# PARADAS.net
KiCad netlist of a schematic drawn in EAGLE
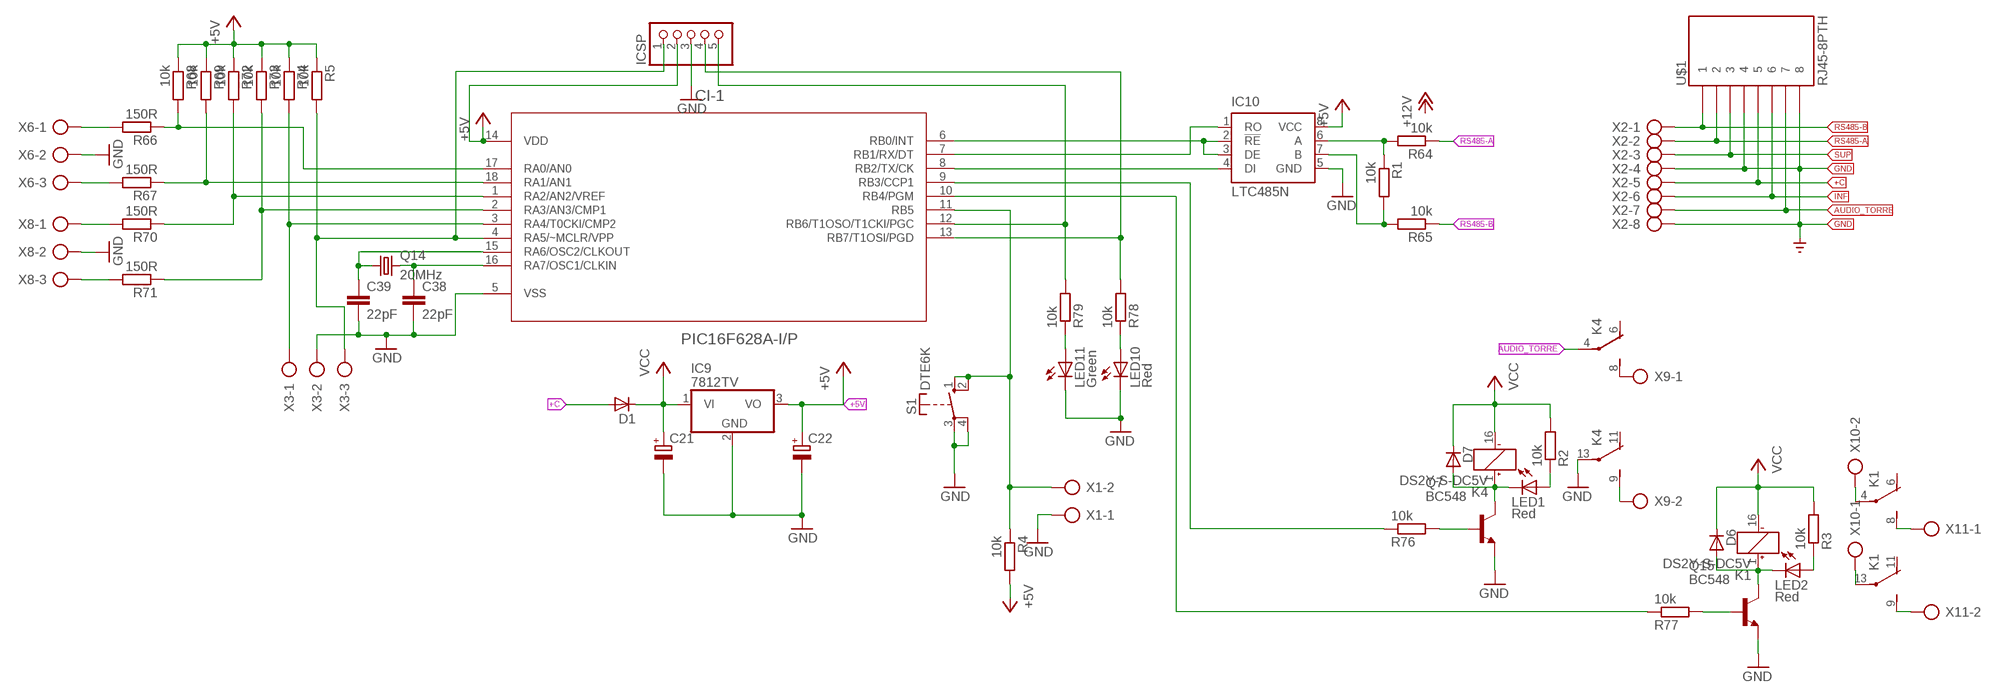
[diagram p0: schematic, sheet 1]

(export (version "E")
  (design (tool "Eeschema 10.0.6"))
  (components
    (comp (ref "C21")
      (value "CPOL-EUE5-13")
      (footprint "eagle-import:E5-13")
      (libsource (lib "eagle-import") (part "CPOL-EUE5-13"))
    )
    (comp (ref "C22")
      (value "CPOL-EUE5-13")
      (footprint "eagle-import:E5-13")
      (libsource (lib "eagle-import") (part "CPOL-EUE5-13"))
    )
    (comp (ref "C38")
      (value "22pF")
      (footprint "eagle-import:C0805")
      (libsource (lib "eagle-import") (part "C-EUC0805"))
    )
    (comp (ref "C39")
      (value "22pF")
      (footprint "eagle-import:C0805")
      (libsource (lib "eagle-import") (part "C-EUC0805"))
    )
    (comp (ref "CI-1")
      (value "PIC16F628A-I/P")
      (footprint "eagle-import:DIP254P762X533-18")
      (libsource (lib "eagle-import") (part "PIC16F628A-I/P"))
    )
    (comp (ref "D1")
      (value "BYS10")
      (footprint "eagle-import:SOD106A")
      (fields (field (name "MPN") "BYS10/45"))
      (libsource (lib "eagle-import") (part "BYS10"))
    )
    (comp (ref "D6")
      (value "BYS10")
      (footprint "eagle-import:SOD106A")
      (fields (field (name "MPN") "BYS10/45"))
      (libsource (lib "eagle-import") (part "BYS10"))
    )
    (comp (ref "D7")
      (value "BYS10")
      (footprint "eagle-import:SOD106A")
      (fields (field (name "MPN") "BYS10/45"))
      (libsource (lib "eagle-import") (part "BYS10"))
    )
    (comp (ref "IC9")
      (value "7812TV")
      (footprint "eagle-import:TO220V")
      (libsource (lib "eagle-import") (part "78TV12"))
    )
    (comp (ref "IC10")
      (value "LTC485N")
      (footprint "eagle-import:DIL08")
      (libsource (lib "eagle-import") (part "LTC485N"))
    )
    (comp (ref "ICSP")
      (value "PINHD-1X5")
      (footprint "eagle-import:1X05")
      (libsource (lib "eagle-import") (part "PINHD-1X5"))
    )
    (comp (ref "K1")
      (value "DS2Y-S-DC5V")
      (footprint "eagle-import:DS2Y")
      (libsource (lib "eagle-import") (part "DS2Y-S-DC5V"))
    )
    (comp (ref "K4")
      (value "DS2Y-S-DC5V")
      (footprint "eagle-import:DS2Y")
      (libsource (lib "eagle-import") (part "DS2Y-S-DC5V"))
    )
    (comp (ref "LED1")
      (value "Red")
      (footprint "eagle-import:LED5MM")
      (libsource (lib "eagle-import") (part "LED5MM"))
    )
    (comp (ref "LED2")
      (value "Red")
      (footprint "eagle-import:LED5MM")
      (libsource (lib "eagle-import") (part "LED5MM"))
    )
    (comp (ref "LED10")
      (value "Red")
      (footprint "eagle-import:LED5MM")
      (libsource (lib "eagle-import") (part "LED5MM"))
    )
    (comp (ref "LED11")
      (value "Green")
      (footprint "eagle-import:LED5MM")
      (libsource (lib "eagle-import") (part "LED5MM"))
    )
    (comp (ref "Q7")
      (value "BC548")
      (footprint "eagle-import:TO92-EBC")
      (libsource (lib "eagle-import") (part "BC548"))
    )
    (comp (ref "Q14")
      (value "20MHz")
      (footprint "eagle-import:HC18U-V")
      (libsource (lib "eagle-import") (part "CRYTALHC18U-V"))
    )
    (comp (ref "Q15")
      (value "BC548")
      (footprint "eagle-import:TO92-EBC")
      (libsource (lib "eagle-import") (part "BC548"))
    )
    (comp (ref "R1")
      (value "10k")
      (footprint "eagle-import:0207_10")
      (libsource (lib "eagle-import") (part "R-EU_0207/10"))
    )
    (comp (ref "R2")
      (value "10k")
      (footprint "eagle-import:0207_10")
      (libsource (lib "eagle-import") (part "R-EU_0207/10"))
    )
    (comp (ref "R3")
      (value "10k")
      (footprint "eagle-import:0207_10")
      (libsource (lib "eagle-import") (part "R-EU_0207/10"))
    )
    (comp (ref "R4")
      (value "10k")
      (footprint "eagle-import:0207_10")
      (libsource (lib "eagle-import") (part "R-EU_0207/10"))
    )
    (comp (ref "R5")
      (value "10k")
      (footprint "eagle-import:0207_10")
      (libsource (lib "eagle-import") (part "R-EU_0207/10"))
    )
    (comp (ref "R64")
      (value "10k")
      (footprint "eagle-import:0207_10")
      (libsource (lib "eagle-import") (part "R-EU_0207/10"))
    )
    (comp (ref "R65")
      (value "10k")
      (footprint "eagle-import:0207_10")
      (libsource (lib "eagle-import") (part "R-EU_0207/10"))
    )
    (comp (ref "R66")
      (value "150R")
      (footprint "eagle-import:0207_10")
      (libsource (lib "eagle-import") (part "R-EU_0207/10"))
    )
    (comp (ref "R67")
      (value "150R")
      (footprint "eagle-import:0207_10")
      (libsource (lib "eagle-import") (part "R-EU_0207/10"))
    )
    (comp (ref "R68")
      (value "10k")
      (footprint "eagle-import:0207_10")
      (libsource (lib "eagle-import") (part "R-EU_0207/10"))
    )
    (comp (ref "R69")
      (value "10k")
      (footprint "eagle-import:0207_10")
      (libsource (lib "eagle-import") (part "R-EU_0207/10"))
    )
    (comp (ref "R70")
      (value "150R")
      (footprint "eagle-import:0207_10")
      (libsource (lib "eagle-import") (part "R-EU_0207/10"))
    )
    (comp (ref "R71")
      (value "150R")
      (footprint "eagle-import:0207_10")
      (libsource (lib "eagle-import") (part "R-EU_0207/10"))
    )
    (comp (ref "R72")
      (value "10k")
      (footprint "eagle-import:0207_10")
      (libsource (lib "eagle-import") (part "R-EU_0207/10"))
    )
    (comp (ref "R73")
      (value "10k")
      (footprint "eagle-import:0207_10")
      (libsource (lib "eagle-import") (part "R-EU_0207/10"))
    )
    (comp (ref "R74")
      (value "10k")
      (footprint "eagle-import:0207_10")
      (libsource (lib "eagle-import") (part "R-EU_0207/10"))
    )
    (comp (ref "R76")
      (value "10k")
      (footprint "eagle-import:0207_10")
      (libsource (lib "eagle-import") (part "R-EU_0207/10"))
    )
    (comp (ref "R77")
      (value "10k")
      (footprint "eagle-import:0207_10")
      (libsource (lib "eagle-import") (part "R-EU_0207/10"))
    )
    (comp (ref "R78")
      (value "10k")
      (footprint "eagle-import:0207_10")
      (libsource (lib "eagle-import") (part "R-EU_0207/10"))
    )
    (comp (ref "R79")
      (value "10k")
      (footprint "eagle-import:0207_10")
      (libsource (lib "eagle-import") (part "R-EU_0207/10"))
    )
    (comp (ref "S1")
      (value "DTE6K")
      (footprint "eagle-import:DTE6K")
      (libsource (lib "eagle-import") (part "DTE6K"))
    )
    (comp (ref "U$1")
      (value "RJ45-8PTH")
      (footprint "eagle-import:RJ45-8")
      (libsource (lib "eagle-import") (part "RJ45-8PTH"))
    )
    (comp (ref "X1")
      (value "AK500/2")
      (footprint "eagle-import:AK500_2")
      (libsource (lib "eagle-import") (part "AK500/2"))
    )
    (comp (ref "X2")
      (value "RS485_CNT")
      (footprint "eagle-import:AK500_8")
      (libsource (lib "eagle-import") (part "AK500/8"))
    )
    (comp (ref "X3")
      (value "AK500/3")
      (footprint "eagle-import:AK500_3")
      (libsource (lib "eagle-import") (part "AK500/3"))
    )
    (comp (ref "X6")
      (value "AK500/3")
      (footprint "eagle-import:AK500_3")
      (libsource (lib "eagle-import") (part "AK500/3"))
    )
    (comp (ref "X8")
      (value "AK500/3")
      (footprint "eagle-import:AK500_3")
      (libsource (lib "eagle-import") (part "AK500/3"))
    )
    (comp (ref "X9")
      (value "AK500/2")
      (footprint "eagle-import:AK500_2")
      (libsource (lib "eagle-import") (part "AK500/2"))
    )
    (comp (ref "X10")
      (value "AK500/2")
      (footprint "eagle-import:AK500_2")
      (libsource (lib "eagle-import") (part "AK500/2"))
    )
    (comp (ref "X11")
      (value "AK500/2")
      (footprint "eagle-import:AK500_2")
      (libsource (lib "eagle-import") (part "AK500/2"))
    )
  )
  (nets
    (net (code "1") (name "+5V") (class "Default")
      (node (ref "C22") (pin "+") (pinfunction "+_+") (pintype "passive"))
      (node (ref "CI-1") (pin "14") (pinfunction "VDD_14") (pintype "power_in"))
      (node (ref "IC10") (pin "8") (pinfunction "VCC_8") (pintype "input"))
      (node (ref "IC9") (pin "3") (pinfunction "VO_3") (pintype "passive"))
      (node (ref "ICSP") (pin "2") (pinfunction "2_2") (pintype "passive"))
      (node (ref "R4") (pin "2") (pinfunction "2_2") (pintype "passive"))
      (node (ref "R5") (pin "1") (pinfunction "1_1") (pintype "passive"))
      (node (ref "R68") (pin "1") (pinfunction "1_1") (pintype "passive"))
      (node (ref "R69") (pin "1") (pinfunction "1_1") (pintype "passive"))
      (node (ref "R72") (pin "1") (pinfunction "1_1") (pintype "passive"))
      (node (ref "R73") (pin "1") (pinfunction "1_1") (pintype "passive"))
      (node (ref "R74") (pin "1") (pinfunction "1_1") (pintype "passive"))
    )
    (net (code "3") (name "+C") (class "Default")
      (node (ref "D1") (pin "A") (pinfunction "A_A") (pintype "passive"))
      (node (ref "U$1") (pin "5") (pinfunction "5_5") (pintype "bidirectional"))
      (node (ref "X2") (pin "5") (pinfunction "KL_5") (pintype "passive"))
    )
    (net (code "4") (name "AUDIO_TORRE") (class "Default")
      (node (ref "K4") (pin "4") (pinfunction "P_4") (pintype "passive"))
      (node (ref "U$1") (pin "7") (pinfunction "7_7") (pintype "bidirectional"))
      (node (ref "X2") (pin "7") (pinfunction "KL_7") (pintype "passive"))
    )
    (net (code "5") (name "GND") (class "Default")
      (node (ref "C21") (pin "-") (pinfunction "-_-") (pintype "passive"))
      (node (ref "C22") (pin "-") (pinfunction "-_-") (pintype "passive"))
      (node (ref "C38") (pin "2") (pinfunction "2_2") (pintype "passive"))
      (node (ref "C39") (pin "2") (pinfunction "2_2") (pintype "passive"))
      (node (ref "CI-1") (pin "5") (pinfunction "VSS_5") (pintype "power_in"))
      (node (ref "IC10") (pin "5") (pinfunction "GND_5") (pintype "input"))
      (node (ref "IC9") (pin "2") (pinfunction "GND_2") (pintype "passive"))
      (node (ref "ICSP") (pin "3") (pinfunction "3_3") (pintype "passive"))
      (node (ref "K4") (pin "13") (pinfunction "P_13") (pintype "passive"))
      (node (ref "LED10") (pin "K") (pinfunction "C_K") (pintype "passive"))
      (node (ref "LED11") (pin "K") (pinfunction "C_K") (pintype "passive"))
      (node (ref "Q15") (pin "E") (pinfunction "E_E") (pintype "passive"))
      (node (ref "Q7") (pin "E") (pinfunction "E_E") (pintype "passive"))
      (node (ref "S1") (pin "3") (pinfunction "P_3") (pintype "passive"))
      (node (ref "S1") (pin "4") (pinfunction "P_4") (pintype "passive"))
      (node (ref "U$1") (pin "4") (pinfunction "4_4") (pintype "bidirectional"))
      (node (ref "U$1") (pin "8") (pinfunction "8_8") (pintype "bidirectional"))
      (node (ref "X1") (pin "1") (pinfunction "KL_1") (pintype "passive"))
      (node (ref "X2") (pin "4") (pinfunction "KL_4") (pintype "passive"))
      (node (ref "X2") (pin "8") (pinfunction "KL_8") (pintype "passive"))
      (node (ref "X3") (pin "2") (pinfunction "KL_2") (pintype "passive"))
      (node (ref "X6") (pin "2") (pinfunction "KL_2") (pintype "passive"))
      (node (ref "X8") (pin "2") (pinfunction "KL_2") (pintype "passive"))
    )
    (net (code "6") (name "INF") (class "Default")
      (node (ref "U$1") (pin "6") (pinfunction "6_6") (pintype "bidirectional"))
      (node (ref "X2") (pin "6") (pinfunction "KL_6") (pintype "passive"))
    )
    (net (code "7") (name "Net-(CI-1-RA0{slash}AN0)") (class "Default")
      (node (ref "CI-1") (pin "17") (pinfunction "RA0/AN0_17") (pintype "bidirectional"))
      (node (ref "R66") (pin "1") (pinfunction "1_1") (pintype "passive"))
      (node (ref "R68") (pin "2") (pinfunction "2_2") (pintype "passive"))
    )
    (net (code "8") (name "Net-(CI-1-RA1{slash}AN1)") (class "Default")
      (node (ref "CI-1") (pin "18") (pinfunction "RA1/AN1_18") (pintype "bidirectional"))
      (node (ref "R67") (pin "1") (pinfunction "1_1") (pintype "passive"))
      (node (ref "R69") (pin "2") (pinfunction "2_2") (pintype "passive"))
    )
    (net (code "9") (name "Net-(CI-1-RA2{slash}AN2{slash}VREF)") (class "Default")
      (node (ref "CI-1") (pin "1") (pinfunction "RA2/AN2/VREF_1") (pintype "bidirectional"))
      (node (ref "R70") (pin "1") (pinfunction "1_1") (pintype "passive"))
      (node (ref "R72") (pin "2") (pinfunction "2_2") (pintype "passive"))
    )
    (net (code "10") (name "Net-(CI-1-RA3{slash}AN3{slash}CMP1)") (class "Default")
      (node (ref "CI-1") (pin "2") (pinfunction "RA3/AN3/CMP1_2") (pintype "bidirectional"))
      (node (ref "R71") (pin "1") (pinfunction "1_1") (pintype "passive"))
      (node (ref "R73") (pin "2") (pinfunction "2_2") (pintype "passive"))
    )
    (net (code "11") (name "Net-(CI-1-RA4{slash}T0CKI{slash}CMP2)") (class "Default")
      (node (ref "CI-1") (pin "3") (pinfunction "RA4/T0CKI/CMP2_3") (pintype "bidirectional"))
      (node (ref "R74") (pin "2") (pinfunction "2_2") (pintype "passive"))
      (node (ref "X3") (pin "1") (pinfunction "KL_1") (pintype "passive"))
    )
    (net (code "12") (name "Net-(CI-1-RA5{slash}~{MCLR{slash}VPP})") (class "Default")
      (node (ref "CI-1") (pin "4") (pinfunction "RA5/~{MCLR/VPP}_4") (pintype "bidirectional"))
      (node (ref "ICSP") (pin "1") (pinfunction "1_1") (pintype "passive"))
      (node (ref "R5") (pin "2") (pinfunction "2_2") (pintype "passive"))
      (node (ref "X3") (pin "3") (pinfunction "KL_3") (pintype "passive"))
    )
    (net (code "13") (name "Net-(CI-1-RA6{slash}OSC2{slash}CLKOUT)") (class "Default")
      (node (ref "C39") (pin "1") (pinfunction "1_1") (pintype "passive"))
      (node (ref "CI-1") (pin "15") (pinfunction "RA6/OSC2/CLKOUT_15") (pintype "bidirectional"))
      (node (ref "Q14") (pin "1") (pinfunction "1_1") (pintype "passive"))
    )
    (net (code "14") (name "Net-(CI-1-RA7{slash}OSC1{slash}CLKIN)") (class "Default")
      (node (ref "C38") (pin "1") (pinfunction "1_1") (pintype "passive"))
      (node (ref "CI-1") (pin "16") (pinfunction "RA7/OSC1/CLKIN_16") (pintype "bidirectional"))
      (node (ref "Q14") (pin "2") (pinfunction "2_2") (pintype "passive"))
    )
    (net (code "15") (name "Net-(CI-1-RB0{slash}INT)") (class "Default")
      (node (ref "CI-1") (pin "6") (pinfunction "RB0/INT_6") (pintype "bidirectional"))
      (node (ref "IC10") (pin "2") (pinfunction "~{RE}_2") (pintype "input"))
      (node (ref "IC10") (pin "3") (pinfunction "DE_3") (pintype "input"))
    )
    (net (code "16") (name "Net-(CI-1-RB1{slash}RX{slash}DT)") (class "Default")
      (node (ref "CI-1") (pin "7") (pinfunction "RB1/RX/DT_7") (pintype "bidirectional"))
      (node (ref "IC10") (pin "1") (pinfunction "RO_1") (pintype "output"))
    )
    (net (code "17") (name "Net-(CI-1-RB2{slash}TX{slash}CK)") (class "Default")
      (node (ref "CI-1") (pin "8") (pinfunction "RB2/TX/CK_8") (pintype "bidirectional"))
      (node (ref "IC10") (pin "4") (pinfunction "DI_4") (pintype "input"))
    )
    (net (code "18") (name "Net-(CI-1-RB3{slash}CCP1)") (class "Default")
      (node (ref "CI-1") (pin "9") (pinfunction "RB3/CCP1_9") (pintype "bidirectional"))
      (node (ref "R76") (pin "1") (pinfunction "1_1") (pintype "passive"))
    )
    (net (code "19") (name "Net-(CI-1-RB4{slash}PGM)") (class "Default")
      (node (ref "CI-1") (pin "10") (pinfunction "RB4/PGM_10") (pintype "bidirectional"))
      (node (ref "R77") (pin "1") (pinfunction "1_1") (pintype "passive"))
    )
    (net (code "20") (name "Net-(CI-1-RB5)") (class "Default")
      (node (ref "CI-1") (pin "11") (pinfunction "RB5_11") (pintype "bidirectional"))
      (node (ref "R4") (pin "1") (pinfunction "1_1") (pintype "passive"))
      (node (ref "S1") (pin "1") (pinfunction "S_1") (pintype "passive"))
      (node (ref "S1") (pin "2") (pinfunction "S_2") (pintype "passive"))
      (node (ref "X1") (pin "2") (pinfunction "KL_2") (pintype "passive"))
    )
    (net (code "21") (name "Net-(CI-1-RB6{slash}T1OSO{slash}T1CKI{slash}PGC)") (class "Default")
      (node (ref "CI-1") (pin "12") (pinfunction "RB6/T1OSO/T1CKI/PGC_12") (pintype "bidirectional"))
      (node (ref "ICSP") (pin "5") (pinfunction "5_5") (pintype "passive"))
      (node (ref "R79") (pin "2") (pinfunction "2_2") (pintype "passive"))
    )
    (net (code "22") (name "Net-(CI-1-RB7{slash}T1OSI{slash}PGD)") (class "Default")
      (node (ref "CI-1") (pin "13") (pinfunction "RB7/T1OSI/PGD_13") (pintype "bidirectional"))
      (node (ref "ICSP") (pin "4") (pinfunction "4_4") (pintype "passive"))
      (node (ref "R78") (pin "2") (pinfunction "2_2") (pintype "passive"))
    )
    (net (code "23") (name "Net-(IC10-A)") (class "Default")
      (node (ref "IC10") (pin "6") (pinfunction "A_6") (pintype "bidirectional"))
      (node (ref "R1") (pin "1") (pinfunction "1_1") (pintype "passive"))
      (node (ref "R64") (pin "2") (pinfunction "2_2") (pintype "passive"))
    )
    (net (code "24") (name "Net-(IC10-B)") (class "Default")
      (node (ref "IC10") (pin "7") (pinfunction "B_7") (pintype "bidirectional"))
      (node (ref "R1") (pin "2") (pinfunction "2_2") (pintype "passive"))
      (node (ref "R65") (pin "2") (pinfunction "2_2") (pintype "passive"))
    )
    (net (code "25") (name "Net-(K1A-+)") (class "Default")
      (node (ref "D6") (pin "A") (pinfunction "A_A") (pintype "passive"))
      (node (ref "K1") (pin "1") (pinfunction "+_1") (pintype "passive"))
      (node (ref "LED2") (pin "K") (pinfunction "C_K") (pintype "passive"))
      (node (ref "Q15") (pin "C") (pinfunction "C_C") (pintype "passive"))
    )
    (net (code "26") (name "Net-(K1B-P)") (class "Default")
      (node (ref "K1") (pin "4") (pinfunction "P_4") (pintype "passive"))
      (node (ref "X10") (pin "2") (pinfunction "KL_2") (pintype "passive"))
    )
    (net (code "27") (name "Net-(K1B-S)") (class "Default")
      (node (ref "K1") (pin "8") (pinfunction "S_8") (pintype "passive"))
      (node (ref "X11") (pin "1") (pinfunction "KL_1") (pintype "passive"))
    )
    (net (code "28") (name "Net-(K1C-P)") (class "Default")
      (node (ref "K1") (pin "13") (pinfunction "P_13") (pintype "passive"))
      (node (ref "X10") (pin "1") (pinfunction "KL_1") (pintype "passive"))
    )
    (net (code "29") (name "Net-(K1C-S)") (class "Default")
      (node (ref "K1") (pin "9") (pinfunction "S_9") (pintype "passive"))
      (node (ref "X11") (pin "2") (pinfunction "KL_2") (pintype "passive"))
    )
    (net (code "30") (name "Net-(K4A-+)") (class "Default")
      (node (ref "D7") (pin "A") (pinfunction "A_A") (pintype "passive"))
      (node (ref "K4") (pin "1") (pinfunction "+_1") (pintype "passive"))
      (node (ref "LED1") (pin "K") (pinfunction "C_K") (pintype "passive"))
      (node (ref "Q7") (pin "C") (pinfunction "C_C") (pintype "passive"))
    )
    (net (code "31") (name "Net-(K4B-S)") (class "Default")
      (node (ref "K4") (pin "8") (pinfunction "S_8") (pintype "passive"))
      (node (ref "X9") (pin "1") (pinfunction "KL_1") (pintype "passive"))
    )
    (net (code "32") (name "Net-(K4C-S)") (class "Default")
      (node (ref "K4") (pin "9") (pinfunction "S_9") (pintype "passive"))
      (node (ref "X9") (pin "2") (pinfunction "KL_2") (pintype "passive"))
    )
    (net (code "33") (name "Net-(LED1-PadA)") (class "Default")
      (node (ref "LED1") (pin "A") (pinfunction "A_A") (pintype "passive"))
      (node (ref "R2") (pin "1") (pinfunction "1_1") (pintype "passive"))
    )
    (net (code "34") (name "Net-(LED2-PadA)") (class "Default")
      (node (ref "LED2") (pin "A") (pinfunction "A_A") (pintype "passive"))
      (node (ref "R3") (pin "1") (pinfunction "1_1") (pintype "passive"))
    )
    (net (code "35") (name "Net-(LED10-PadA)") (class "Default")
      (node (ref "LED10") (pin "A") (pinfunction "A_A") (pintype "passive"))
      (node (ref "R78") (pin "1") (pinfunction "1_1") (pintype "passive"))
    )
    (net (code "36") (name "Net-(LED11-PadA)") (class "Default")
      (node (ref "LED11") (pin "A") (pinfunction "A_A") (pintype "passive"))
      (node (ref "R79") (pin "1") (pinfunction "1_1") (pintype "passive"))
    )
    (net (code "37") (name "Net-(Q7-PadB)") (class "Default")
      (node (ref "Q7") (pin "B") (pinfunction "B_B") (pintype "passive"))
      (node (ref "R76") (pin "2") (pinfunction "2_2") (pintype "passive"))
    )
    (net (code "38") (name "Net-(Q15-PadB)") (class "Default")
      (node (ref "Q15") (pin "B") (pinfunction "B_B") (pintype "passive"))
      (node (ref "R77") (pin "2") (pinfunction "2_2") (pintype "passive"))
    )
    (net (code "39") (name "Net-(X6A-KL)") (class "Default")
      (node (ref "R66") (pin "2") (pinfunction "2_2") (pintype "passive"))
      (node (ref "X6") (pin "1") (pinfunction "KL_1") (pintype "passive"))
    )
    (net (code "40") (name "Net-(X6C-KL)") (class "Default")
      (node (ref "R67") (pin "2") (pinfunction "2_2") (pintype "passive"))
      (node (ref "X6") (pin "3") (pinfunction "KL_3") (pintype "passive"))
    )
    (net (code "41") (name "Net-(X8A-KL)") (class "Default")
      (node (ref "R70") (pin "2") (pinfunction "2_2") (pintype "passive"))
      (node (ref "X8") (pin "1") (pinfunction "KL_1") (pintype "passive"))
    )
    (net (code "42") (name "Net-(X8C-KL)") (class "Default")
      (node (ref "R71") (pin "2") (pinfunction "2_2") (pintype "passive"))
      (node (ref "X8") (pin "3") (pinfunction "KL_3") (pintype "passive"))
    )
    (net (code "43") (name "RS485-A") (class "Default")
      (node (ref "R64") (pin "1") (pinfunction "1_1") (pintype "passive"))
      (node (ref "U$1") (pin "2") (pinfunction "2_2") (pintype "bidirectional"))
      (node (ref "X2") (pin "2") (pinfunction "KL_2") (pintype "passive"))
    )
    (net (code "44") (name "RS485-B") (class "Default")
      (node (ref "R65") (pin "1") (pinfunction "1_1") (pintype "passive"))
      (node (ref "U$1") (pin "1") (pinfunction "1_1") (pintype "bidirectional"))
      (node (ref "X2") (pin "1") (pinfunction "KL_1") (pintype "passive"))
    )
    (net (code "45") (name "SUP") (class "Default")
      (node (ref "U$1") (pin "3") (pinfunction "3_3") (pintype "bidirectional"))
      (node (ref "X2") (pin "3") (pinfunction "KL_3") (pintype "passive"))
    )
    (net (code "46") (name "VCC") (class "Default")
      (node (ref "C21") (pin "+") (pinfunction "+_+") (pintype "passive"))
      (node (ref "D1") (pin "K") (pinfunction "K_K") (pintype "passive"))
      (node (ref "D6") (pin "K") (pinfunction "K_K") (pintype "passive"))
      (node (ref "D7") (pin "K") (pinfunction "K_K") (pintype "passive"))
      (node (ref "IC9") (pin "1") (pinfunction "VI_1") (pintype "input"))
      (node (ref "K1") (pin "16") (pinfunction "-_16") (pintype "passive"))
      (node (ref "K4") (pin "16") (pinfunction "-_16") (pintype "passive"))
      (node (ref "R2") (pin "2") (pinfunction "2_2") (pintype "passive"))
      (node (ref "R3") (pin "2") (pinfunction "2_2") (pintype "passive"))
    )
    (net (code "47") (name "unconnected-(K1B-O-Pad6)") (class "Default")
      (node (ref "K1") (pin "6") (pinfunction "O_6") (pintype "passive"))
    )
    (net (code "48") (name "unconnected-(K1C-O-Pad11)") (class "Default")
      (node (ref "K1") (pin "11") (pinfunction "O_11") (pintype "passive"))
    )
    (net (code "49") (name "unconnected-(K4B-O-Pad6)") (class "Default")
      (node (ref "K4") (pin "6") (pinfunction "O_6") (pintype "passive"))
    )
    (net (code "50") (name "unconnected-(K4C-O-Pad11)") (class "Default")
      (node (ref "K4") (pin "11") (pinfunction "O_11") (pintype "passive"))
    )
  )
)
